# Input_Filter.net
KiCad netlist of a schematic drawn in Altium Designer
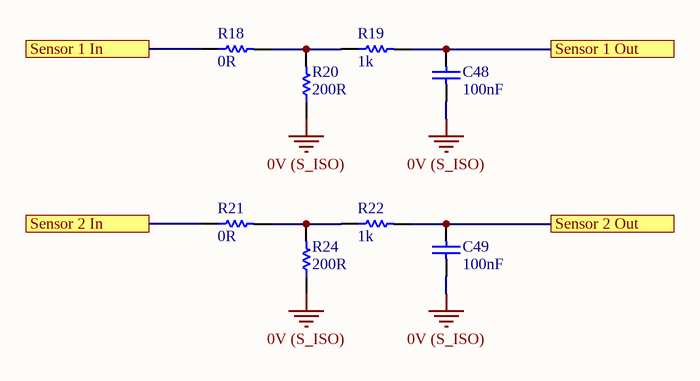
[diagram p0: Input Filter.SchDoc]

(export (version "E")
  (design (tool "Eeschema 10.0.6"))
  (components
    (comp (ref "C48")
      (value "100nF")
      (footprint "0805")
      (fields
        (field (name "PART NUMBER") "GCM21BR71E104KA37L")
        (field (name "TOLERANCE") "10%")
        (field (name "MANUFACTURER") "muRata")
      )
      (libsource (lib "ts_20-standard-library") (part "Capacitor"))
    )
    (comp (ref "C49")
      (value "100nF")
      (footprint "0805")
      (fields
        (field (name "PART NUMBER") "GCM21BR71E104KA37L")
        (field (name "TOLERANCE") "10%")
        (field (name "MANUFACTURER") "muRata")
      )
      (libsource (lib "ts_20-standard-library") (part "Capacitor"))
    )
    (comp (ref "R18")
      (value "0R")
      (footprint "0805")
      (fields
        (field (name "PART NUMBER") "RC0805FR070RL")
        (field (name "MANUFACTURER") "YAGEO")
        (field (name "TOLERANCE") "0.01")
      )
      (libsource (lib "ts_20-standard-library") (part "Resistor"))
    )
    (comp (ref "R19")
      (value "1k")
      (footprint "0805")
      (fields
        (field (name "PART NUMBER") "RC0805FR071KL")
        (field (name "MANUFACTURER") "YAGEO")
        (field (name "TOLERANCE") "0.01")
      )
      (libsource (lib "ts_20-standard-library") (part "Resistor"))
    )
    (comp (ref "R20")
      (value "200R")
      (footprint "0805")
      (fields
        (field (name "PART NUMBER") "RC0805FR07200RL")
        (field (name "MANUFACTURER") "YAGEO")
        (field (name "TOLERANCE") "0.01")
      )
      (libsource (lib "ts_20-standard-library") (part "Resistor"))
    )
    (comp (ref "R21")
      (value "0R")
      (footprint "0805")
      (fields
        (field (name "PART NUMBER") "RC0805FR070RL")
        (field (name "MANUFACTURER") "YAGEO")
        (field (name "TOLERANCE") "0.01")
      )
      (libsource (lib "ts_20-standard-library") (part "Resistor"))
    )
    (comp (ref "R22")
      (value "1k")
      (footprint "0805")
      (fields
        (field (name "PART NUMBER") "RC0805FR071KL")
        (field (name "MANUFACTURER") "YAGEO")
        (field (name "TOLERANCE") "0.01")
      )
      (libsource (lib "ts_20-standard-library") (part "Resistor"))
    )
    (comp (ref "R24")
      (value "200R")
      (footprint "0805")
      (fields
        (field (name "PART NUMBER") "RC0805FR07200RL")
        (field (name "MANUFACTURER") "YAGEO")
        (field (name "TOLERANCE") "0.01")
      )
      (libsource (lib "ts_20-standard-library") (part "Resistor"))
    )
  )
  (nets
    (net (code "1") (name "/Sensor 1 In") (class "Default")
      (node (ref "R18") (pin "1") (pinfunction "1_1") (pintype "passive"))
    )
    (net (code "2") (name "/Sensor 1 Out") (class "Default")
      (node (ref "C48") (pin "2") (pinfunction "2_2") (pintype "passive"))
      (node (ref "R19") (pin "2") (pinfunction "2_2") (pintype "passive"))
    )
    (net (code "3") (name "/Sensor 2 In") (class "Default")
      (node (ref "R21") (pin "1") (pinfunction "1_1") (pintype "passive"))
    )
    (net (code "4") (name "/Sensor 2 Out") (class "Default")
      (node (ref "C49") (pin "2") (pinfunction "2_2") (pintype "passive"))
      (node (ref "R22") (pin "2") (pinfunction "2_2") (pintype "passive"))
    )
    (net (code "5") (name "0V (S_ISO)") (class "Default")
      (node (ref "C48") (pin "1") (pinfunction "1_1") (pintype "passive"))
      (node (ref "C49") (pin "1") (pinfunction "1_1") (pintype "passive"))
      (node (ref "R20") (pin "1") (pinfunction "1_1") (pintype "passive"))
      (node (ref "R24") (pin "1") (pinfunction "1_1") (pintype "passive"))
    )
    (net (code "6") (name "Net-(R18-Pad2)") (class "Default")
      (node (ref "R18") (pin "2") (pinfunction "2_2") (pintype "passive"))
      (node (ref "R19") (pin "1") (pinfunction "1_1") (pintype "passive"))
      (node (ref "R20") (pin "2") (pinfunction "2_2") (pintype "passive"))
    )
    (net (code "7") (name "Net-(R21-Pad2)") (class "Default")
      (node (ref "R21") (pin "2") (pinfunction "2_2") (pintype "passive"))
      (node (ref "R22") (pin "1") (pinfunction "1_1") (pintype "passive"))
      (node (ref "R24") (pin "2") (pinfunction "2_2") (pintype "passive"))
    )
  )
)
